# chipjabber-bbi-probe.net
KiCad netlist of a schematic drawn in Altium Designer
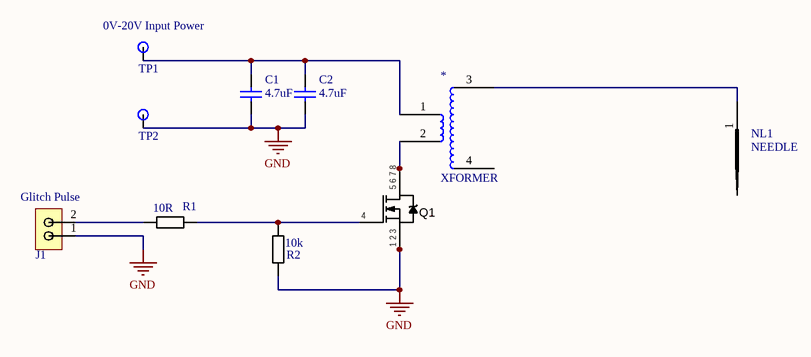
[diagram p0: chipjabber-bbi-probe.SchDoc]

(export (version "E")
  (design (tool "Eeschema 10.0.6"))
  (components
    (comp (ref "*")
      (value "XFORMER")
      (footprint "bbilibs:XFORMER")
      (libsource (lib "bbilibs") (part "XFORMER"))
    )
    (comp (ref "C1")
      (value "4.7uF")
      (footprint "CAPC0805_M")
      (description "4u7, 50V, 0805, Ceramic")
      (fields (field (name "PART NUMBER") "CCHIP-4u7-0805-50V") (field (name "TOLERANCE") "10%"))
      (libsource (lib "NewAE_AltiumLib") (part "CAP"))
    )
    (comp (ref "C2")
      (value "4.7uF")
      (footprint "CAPC0805_M")
      (description "4u7, 50V, 0805, Ceramic")
      (fields (field (name "PART NUMBER") "CCHIP-4u7-0805-50V") (field (name "TOLERANCE") "10%"))
      (libsource (lib "NewAE_AltiumLib") (part "CAP"))
    )
    (comp (ref "J1")
      (value "Power_Header")
      (footprint "76382-302LF")
      (description "CONN HEADER 2POS .100\" R/A GOLD")
      (fields (field (name "PART NUMBER") "2_PIN_RIGHT_POWER"))
      (libsource (lib "NewAE_AltiumLib") (part "1x2_Pin_Header"))
    )
    (comp (ref "NL1") (value "NEEDLE") (footprint "PIN") (libsource (lib "bbilibs") (part "NEEDLE")))
    (comp (ref "Q1")
      (value "IRF7807ZTRPBF")
      (footprint "SOIC8_NARROW")
      (description "MOSFET, N-Channel, 8-SOIC, Logic Level")
      (libsource (lib "NewAE_AltiumLib") (part "MOSFET_NCH_8SOIC"))
    )
    (comp (ref "R1")
      (value "10R")
      (footprint "RESC1608X55N")
      (description "10R res, 0603, 1%, 1/10W")
      (fields (field (name "PART NUMBER") "RCHIP-10R-0603") (field (name "TOLERANCE") "1%"))
      (libsource (lib "NewAE_AltiumLib") (part "RES-EU"))
    )
    (comp (ref "R2")
      (value "10k")
      (footprint "RESC1608X55N")
      (description "10k res, 0603, 1%, 1/10W")
      (fields (field (name "PART NUMBER") "RCHIP-10K-0603") (field (name "TOLERANCE") "1%"))
      (libsource (lib "") (part "RES-EU_1"))
    )
    (comp (ref "TP1")
      (value "5009")
      (footprint "KEYSTONE5009")
      (description "TEST POINT PC COMPACT .063\"D YEL")
      (fields (field (name "PART NUMBER") "KEYSTONE_5009"))
      (libsource (lib "NewAE_AltiumLib") (part "KEYSTONE_5009"))
    )
    (comp (ref "TP2")
      (value "5011")
      (footprint "KEYSTONE5011")
      (description "TEST POINT PC MULTI PURPOSE BLK")
      (fields (field (name "PART NUMBER") "KEYSTONE_5011"))
      (libsource (lib "NewAE_AltiumLib") (part "KEYSTONE_5011"))
    )
  )
  (nets
    (net (code "1") (name "GND") (class "Default")
      (node (ref "C1") (pin "2") (pinfunction "2_2") (pintype "passive"))
      (node (ref "C2") (pin "2") (pinfunction "2_2") (pintype "passive"))
      (node (ref "J1") (pin "1") (pinfunction "1_1") (pintype "passive"))
      (node (ref "Q1") (pin "1") (pinfunction "1,2,3_1") (pintype "passive"))
      (node (ref "Q1") (pin "2") (pinfunction "S_2") (pintype "passive"))
      (node (ref "Q1") (pin "3") (pinfunction "S_3") (pintype "passive"))
      (node (ref "R2") (pin "2") (pinfunction "2_2") (pintype "passive"))
      (node (ref "TP2") (pin "1") (pinfunction "1_1") (pintype "passive"))
    )
    (net (code "2") (name "Net-(*-Pad1)") (class "Default")
      (node (ref "*") (pin "1") (pinfunction "1_1") (pintype "passive"))
      (node (ref "C1") (pin "1") (pinfunction "1_1") (pintype "passive"))
      (node (ref "C2") (pin "1") (pinfunction "1_1") (pintype "passive"))
      (node (ref "TP1") (pin "1") (pinfunction "1_1") (pintype "passive"))
    )
    (net (code "3") (name "Net-(*-Pad3)") (class "Default")
      (node (ref "*") (pin "3") (pinfunction "3_3") (pintype "passive"))
      (node (ref "NL1") (pin "1") (pinfunction "1_1") (pintype "passive"))
    )
    (net (code "4") (name "Net-(J1-Pad2)") (class "Default")
      (node (ref "J1") (pin "2") (pinfunction "2_2") (pintype "passive"))
      (node (ref "R1") (pin "1") (pinfunction "1_1") (pintype "passive"))
    )
    (net (code "5") (name "Net-(Q1-5,6,7,8)") (class "Default")
      (node (ref "*") (pin "2") (pinfunction "2_2") (pintype "passive"))
      (node (ref "Q1") (pin "5") (pinfunction "5,6,7,8_5") (pintype "passive"))
      (node (ref "Q1") (pin "6") (pinfunction "D_6") (pintype "passive"))
      (node (ref "Q1") (pin "7") (pinfunction "D_7") (pintype "passive"))
      (node (ref "Q1") (pin "8") (pinfunction "D_8") (pintype "passive"))
    )
    (net (code "6") (name "Net-(Q1-G)") (class "Default")
      (node (ref "Q1") (pin "4") (pinfunction "G_4") (pintype "passive"))
      (node (ref "R1") (pin "2") (pinfunction "2_2") (pintype "passive"))
      (node (ref "R2") (pin "1") (pinfunction "1_1") (pintype "passive"))
    )
    (net (code "7") (name "unconnected-(*-Pad4)") (class "Default")
      (node (ref "*") (pin "4") (pinfunction "4_4") (pintype "passive"))
    )
  )
)
